# watch_rev3.net
KiCad netlist of a schematic drawn in EAGLE
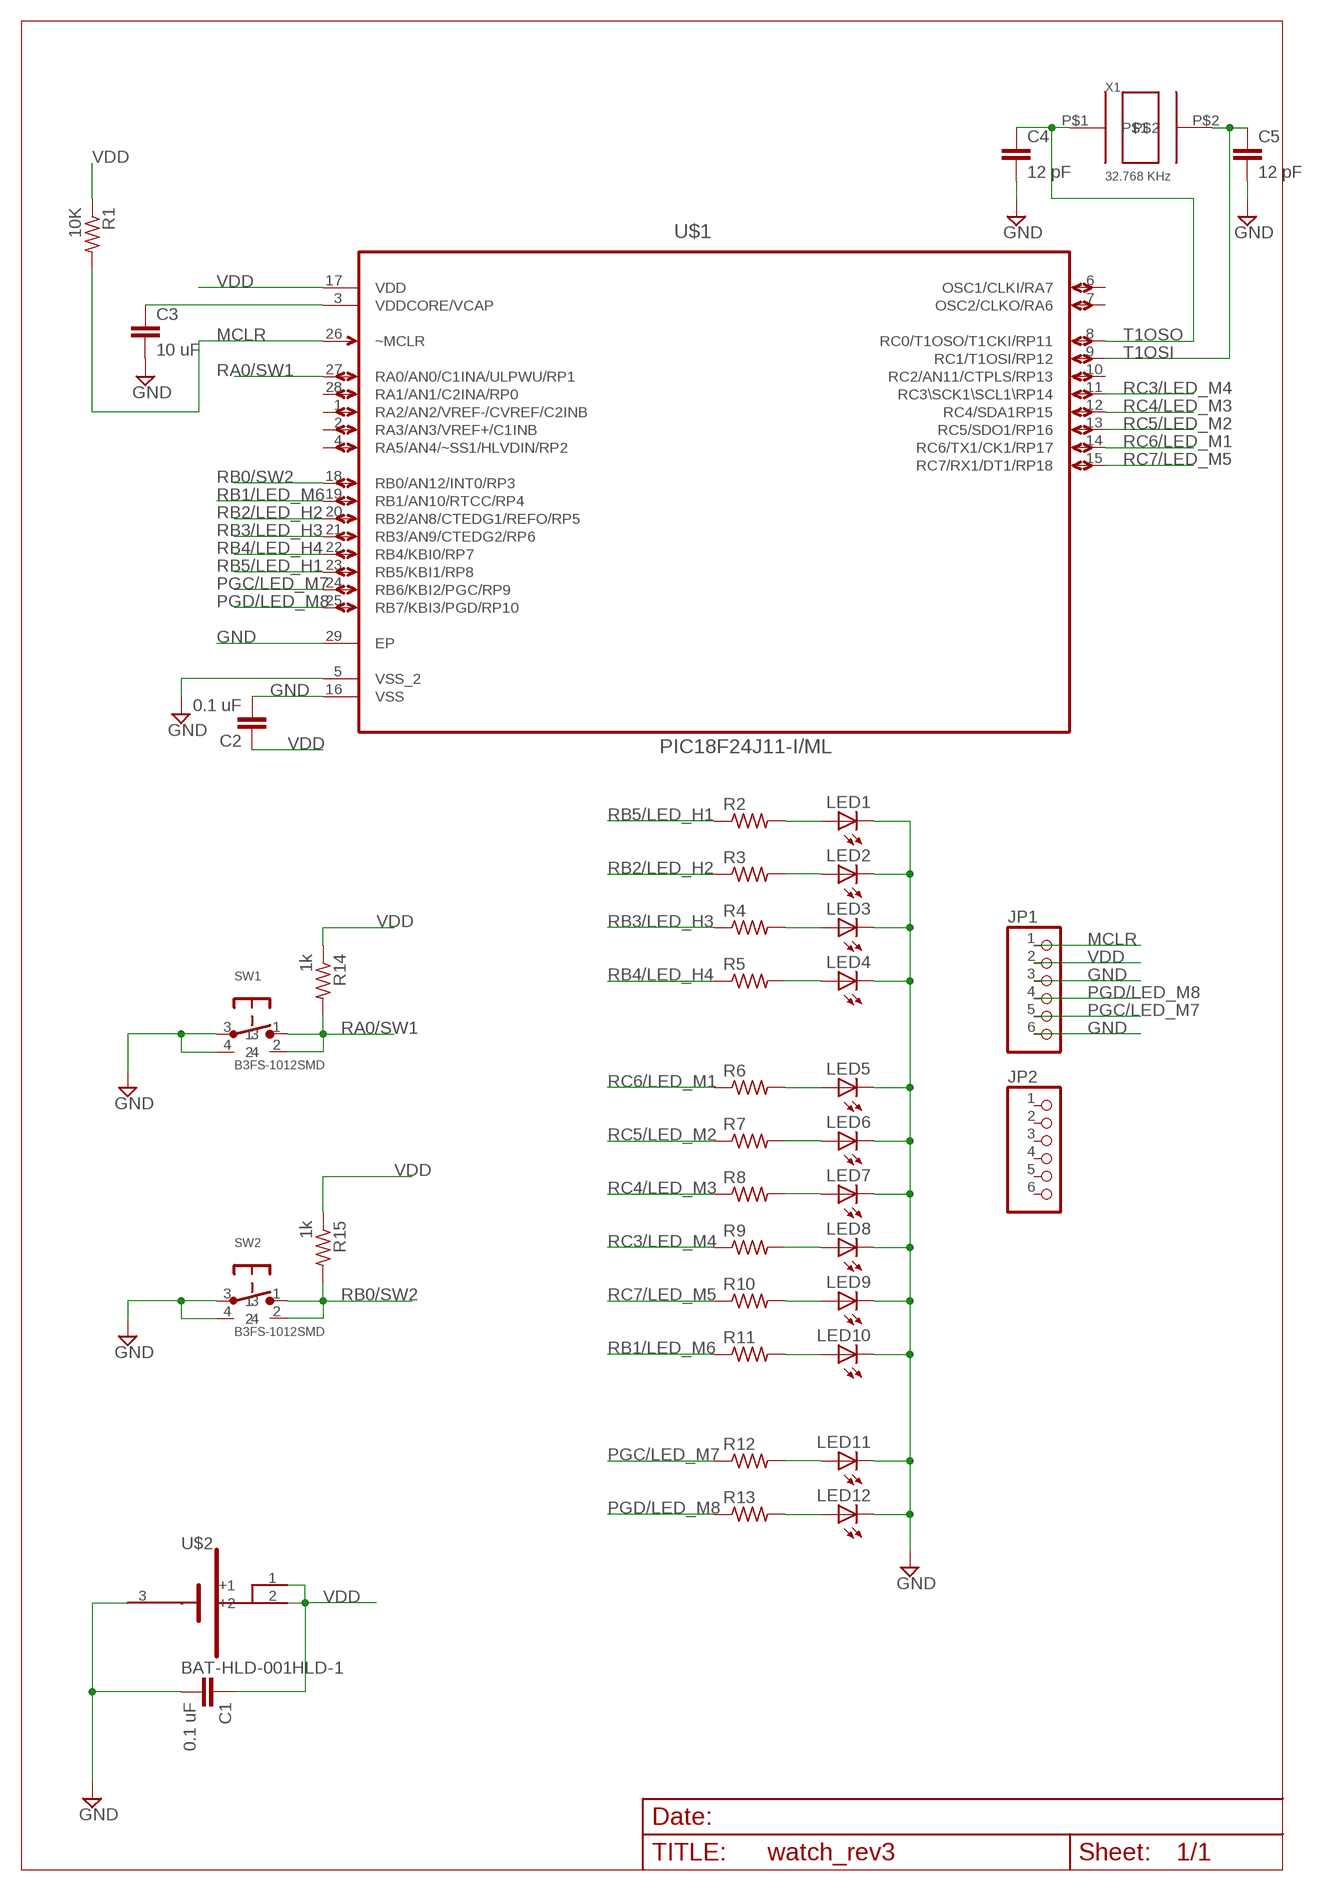
[diagram p0: schematic, sheet 1]

(export (version "E")
  (design (tool "Eeschema 10.0.6"))
  (components
    (comp (ref "C1")
      (value "0.1 uF")
      (footprint "eagle-import:C0603")
      (libsource (lib "eagle-import") (part "C-EUC0603"))
    )
    (comp (ref "C2")
      (value "0.1 uF")
      (footprint "eagle-import:C0603")
      (libsource (lib "eagle-import") (part "C-EUC0603"))
    )
    (comp (ref "C3")
      (value "10 uF")
      (footprint "eagle-import:C0603")
      (libsource (lib "eagle-import") (part "C-EUC0603"))
    )
    (comp (ref "C4")
      (value "12 pF")
      (footprint "eagle-import:C0603")
      (libsource (lib "eagle-import") (part "C-EUC0603"))
    )
    (comp (ref "C5")
      (value "12 pF")
      (footprint "eagle-import:C0603")
      (libsource (lib "eagle-import") (part "C-EUC0603"))
    )
    (comp (ref "JP1")
      (value "PINHD-1X6")
      (footprint "eagle-import:1X06")
      (libsource (lib "eagle-import") (part "PINHD-1X6"))
    )
    (comp (ref "JP2")
      (value "PINHD-1X6")
      (footprint "eagle-import:1X06")
      (libsource (lib "eagle-import") (part "PINHD-1X6"))
    )
    (comp (ref "LED1")
      (value "LEDCHIPLED_0603")
      (footprint "eagle-import:CHIPLED_0603")
      (libsource (lib "eagle-import") (part "LEDCHIPLED_0603"))
    )
    (comp (ref "LED2")
      (value "LEDCHIPLED_0603")
      (footprint "eagle-import:CHIPLED_0603")
      (libsource (lib "eagle-import") (part "LEDCHIPLED_0603"))
    )
    (comp (ref "LED3")
      (value "LEDCHIPLED_0603")
      (footprint "eagle-import:CHIPLED_0603")
      (libsource (lib "eagle-import") (part "LEDCHIPLED_0603"))
    )
    (comp (ref "LED4")
      (value "LEDCHIPLED_0603")
      (footprint "eagle-import:CHIPLED_0603")
      (libsource (lib "eagle-import") (part "LEDCHIPLED_0603"))
    )
    (comp (ref "LED5")
      (value "LEDCHIPLED_0603")
      (footprint "eagle-import:CHIPLED_0603")
      (libsource (lib "eagle-import") (part "LEDCHIPLED_0603"))
    )
    (comp (ref "LED6")
      (value "LEDCHIPLED_0603")
      (footprint "eagle-import:CHIPLED_0603")
      (libsource (lib "eagle-import") (part "LEDCHIPLED_0603"))
    )
    (comp (ref "LED7")
      (value "LEDCHIPLED_0603")
      (footprint "eagle-import:CHIPLED_0603")
      (libsource (lib "eagle-import") (part "LEDCHIPLED_0603"))
    )
    (comp (ref "LED8")
      (value "LEDCHIPLED_0603")
      (footprint "eagle-import:CHIPLED_0603")
      (libsource (lib "eagle-import") (part "LEDCHIPLED_0603"))
    )
    (comp (ref "LED9")
      (value "LEDCHIPLED_0603")
      (footprint "eagle-import:CHIPLED_0603")
      (libsource (lib "eagle-import") (part "LEDCHIPLED_0603"))
    )
    (comp (ref "LED10")
      (value "LEDCHIPLED_0603")
      (footprint "eagle-import:CHIPLED_0603")
      (libsource (lib "eagle-import") (part "LEDCHIPLED_0603"))
    )
    (comp (ref "LED11")
      (value "LEDCHIPLED_0603")
      (footprint "eagle-import:CHIPLED_0603")
      (libsource (lib "eagle-import") (part "LEDCHIPLED_0603"))
    )
    (comp (ref "LED12")
      (value "LEDCHIPLED_0603")
      (footprint "eagle-import:CHIPLED_0603")
      (libsource (lib "eagle-import") (part "LEDCHIPLED_0603"))
    )
    (comp (ref "R1")
      (value "10K")
      (footprint "eagle-import:R0603")
      (libsource (lib "eagle-import") (part "R-US_R0603"))
    )
    (comp (ref "R2")
      (value "R-US_R0603")
      (footprint "eagle-import:R0603")
      (libsource (lib "eagle-import") (part "R-US_R0603"))
    )
    (comp (ref "R3")
      (value "R-US_R0603")
      (footprint "eagle-import:R0603")
      (libsource (lib "eagle-import") (part "R-US_R0603"))
    )
    (comp (ref "R4")
      (value "R-US_R0603")
      (footprint "eagle-import:R0603")
      (libsource (lib "eagle-import") (part "R-US_R0603"))
    )
    (comp (ref "R5")
      (value "R-US_R0603")
      (footprint "eagle-import:R0603")
      (libsource (lib "eagle-import") (part "R-US_R0603"))
    )
    (comp (ref "R6")
      (value "R-US_R0603")
      (footprint "eagle-import:R0603")
      (libsource (lib "eagle-import") (part "R-US_R0603"))
    )
    (comp (ref "R7")
      (value "R-US_R0603")
      (footprint "eagle-import:R0603")
      (libsource (lib "eagle-import") (part "R-US_R0603"))
    )
    (comp (ref "R8")
      (value "R-US_R0603")
      (footprint "eagle-import:R0603")
      (libsource (lib "eagle-import") (part "R-US_R0603"))
    )
    (comp (ref "R9")
      (value "R-US_R0603")
      (footprint "eagle-import:R0603")
      (libsource (lib "eagle-import") (part "R-US_R0603"))
    )
    (comp (ref "R10")
      (value "R-US_R0603")
      (footprint "eagle-import:R0603")
      (libsource (lib "eagle-import") (part "R-US_R0603"))
    )
    (comp (ref "R11")
      (value "R-US_R0603")
      (footprint "eagle-import:R0603")
      (libsource (lib "eagle-import") (part "R-US_R0603"))
    )
    (comp (ref "R12")
      (value "R-US_R0603")
      (footprint "eagle-import:R0603")
      (libsource (lib "eagle-import") (part "R-US_R0603"))
    )
    (comp (ref "R13")
      (value "R-US_R0603")
      (footprint "eagle-import:R0603")
      (libsource (lib "eagle-import") (part "R-US_R0603"))
    )
    (comp (ref "R14")
      (value "1k")
      (footprint "eagle-import:R0603")
      (libsource (lib "eagle-import") (part "R-US_R0603"))
    )
    (comp (ref "R15")
      (value "1k")
      (footprint "eagle-import:R0603")
      (libsource (lib "eagle-import") (part "R-US_R0603"))
    )
    (comp (ref "SW1")
      (value "B3FS-1012SMD")
      (footprint "eagle-import:B3FS-1012")
      (libsource (lib "eagle-import") (part "B3FS-1012SMD"))
    )
    (comp (ref "SW2")
      (value "B3FS-1012SMD")
      (footprint "eagle-import:B3FS-1012")
      (libsource (lib "eagle-import") (part "B3FS-1012SMD"))
    )
    (comp (ref "U$1")
      (value "PIC18F24J11-I/ML")
      (footprint "eagle-import:QFN65P600X600X100-29N")
      (fields (field (name "MPN") "PIC18F24J11-I/Ml"))
      (libsource (lib "eagle-import") (part "PIC18F24J11-I/ML"))
    )
    (comp (ref "U$2")
      (value "BAT-HLD-001HLD-1")
      (footprint "eagle-import:BAT-HLD-001")
      (libsource (lib "eagle-import") (part "BAT-HLD-001HLD-1"))
    )
    (comp (ref "X1")
      (value "32.768 KHz")
      (footprint "eagle-import:XTAL_3.2X1.5")
      (libsource (lib "eagle-import") (part "ST3215SB32768E0HPWBB"))
    )
  )
  (nets
    (net (code "1") (name "/MCLR") (class "Default")
      (node (ref "JP1") (pin "1") (pinfunction "1_1") (pintype "passive"))
      (node (ref "R1") (pin "2") (pinfunction "2_2") (pintype "passive"))
      (node (ref "U$1") (pin "26") (pinfunction "~{MCLR}_26") (pintype "input"))
    )
    (net (code "2") (name "/PGC{slash}LED_M7") (class "Default")
      (node (ref "JP1") (pin "5") (pinfunction "5_5") (pintype "passive"))
      (node (ref "R12") (pin "1") (pinfunction "1_1") (pintype "passive"))
      (node (ref "U$1") (pin "24") (pinfunction "RB6/KBI2/PGC/RP9_24") (pintype "bidirectional"))
    )
    (net (code "3") (name "/PGD{slash}LED_M8") (class "Default")
      (node (ref "JP1") (pin "4") (pinfunction "4_4") (pintype "passive"))
      (node (ref "R13") (pin "1") (pinfunction "1_1") (pintype "passive"))
      (node (ref "U$1") (pin "25") (pinfunction "RB7/KBI3/PGD/RP10_25") (pintype "bidirectional"))
    )
    (net (code "4") (name "/RA0{slash}SW1") (class "Default")
      (node (ref "R14") (pin "2") (pinfunction "2_2") (pintype "passive"))
      (node (ref "SW1") (pin "1") (pinfunction "1_1") (pintype "bidirectional"))
      (node (ref "SW1") (pin "2") (pinfunction "2_2") (pintype "bidirectional"))
      (node (ref "U$1") (pin "27") (pinfunction "RA0/AN0/C1INA/ULPWU/RP1_27") (pintype "bidirectional"))
    )
    (net (code "5") (name "/RB0{slash}SW2") (class "Default")
      (node (ref "R15") (pin "2") (pinfunction "2_2") (pintype "passive"))
      (node (ref "SW2") (pin "1") (pinfunction "1_1") (pintype "bidirectional"))
      (node (ref "SW2") (pin "2") (pinfunction "2_2") (pintype "bidirectional"))
      (node (ref "U$1") (pin "18") (pinfunction "RB0/AN12/INT0/RP3_18") (pintype "bidirectional"))
    )
    (net (code "6") (name "/RB1{slash}LED_M6") (class "Default")
      (node (ref "R11") (pin "1") (pinfunction "1_1") (pintype "passive"))
      (node (ref "U$1") (pin "19") (pinfunction "RB1/AN10/RTCC/RP4_19") (pintype "bidirectional"))
    )
    (net (code "7") (name "/RB2{slash}LED_H2") (class "Default")
      (node (ref "R3") (pin "1") (pinfunction "1_1") (pintype "passive"))
      (node (ref "U$1") (pin "20") (pinfunction "RB2/AN8/CTEDG1/REFO/RP5_20") (pintype "bidirectional"))
    )
    (net (code "8") (name "/RB3{slash}LED_H3") (class "Default")
      (node (ref "R4") (pin "1") (pinfunction "1_1") (pintype "passive"))
      (node (ref "U$1") (pin "21") (pinfunction "RB3/AN9/CTEDG2/RP6_21") (pintype "bidirectional"))
    )
    (net (code "9") (name "/RB4{slash}LED_H4") (class "Default")
      (node (ref "R5") (pin "1") (pinfunction "1_1") (pintype "passive"))
      (node (ref "U$1") (pin "22") (pinfunction "RB4/KBI0/RP7_22") (pintype "bidirectional"))
    )
    (net (code "10") (name "/RB5{slash}LED_H1") (class "Default")
      (node (ref "R2") (pin "1") (pinfunction "1_1") (pintype "passive"))
      (node (ref "U$1") (pin "23") (pinfunction "RB5/KBI1/RP8_23") (pintype "bidirectional"))
    )
    (net (code "11") (name "/RC3{slash}LED_M4") (class "Default")
      (node (ref "R9") (pin "1") (pinfunction "1_1") (pintype "passive"))
      (node (ref "U$1") (pin "11") (pinfunction "RC3\\SCK1\\SCL1\\RP14_11") (pintype "bidirectional"))
    )
    (net (code "12") (name "/RC4{slash}LED_M3") (class "Default")
      (node (ref "R8") (pin "1") (pinfunction "1_1") (pintype "passive"))
      (node (ref "U$1") (pin "12") (pinfunction "RC4/SDA1RP15_12") (pintype "bidirectional"))
    )
    (net (code "13") (name "/RC5{slash}LED_M2") (class "Default")
      (node (ref "R7") (pin "1") (pinfunction "1_1") (pintype "passive"))
      (node (ref "U$1") (pin "13") (pinfunction "RC5/SDO1/RP16_13") (pintype "bidirectional"))
    )
    (net (code "14") (name "/RC6{slash}LED_M1") (class "Default")
      (node (ref "R6") (pin "1") (pinfunction "1_1") (pintype "passive"))
      (node (ref "U$1") (pin "14") (pinfunction "RC6/TX1/CK1/RP17_14") (pintype "bidirectional"))
    )
    (net (code "15") (name "/RC7{slash}LED_M5") (class "Default")
      (node (ref "R10") (pin "1") (pinfunction "1_1") (pintype "passive"))
      (node (ref "U$1") (pin "15") (pinfunction "RC7/RX1/DT1/RP18_15") (pintype "bidirectional"))
    )
    (net (code "16") (name "/T1OSI") (class "Default")
      (node (ref "C5") (pin "1") (pinfunction "1_1") (pintype "passive"))
      (node (ref "U$1") (pin "9") (pinfunction "RC1/T1OSI/RP12_9") (pintype "bidirectional"))
      (node (ref "X1") (pin "P$2") (pinfunction "P$2_P$2") (pintype "bidirectional"))
    )
    (net (code "17") (name "/T1OSO") (class "Default")
      (node (ref "C4") (pin "1") (pinfunction "1_1") (pintype "passive"))
      (node (ref "U$1") (pin "8") (pinfunction "RC0/T1OSO/T1CKI/RP11_8") (pintype "bidirectional"))
      (node (ref "X1") (pin "P$1") (pinfunction "P$1_P$1") (pintype "bidirectional"))
    )
    (net (code "18") (name "/VDD") (class "Default")
      (node (ref "C1") (pin "1") (pinfunction "1_1") (pintype "passive"))
      (node (ref "C2") (pin "1") (pinfunction "1_1") (pintype "passive"))
      (node (ref "JP1") (pin "2") (pinfunction "2_2") (pintype "passive"))
      (node (ref "R1") (pin "1") (pinfunction "1_1") (pintype "passive"))
      (node (ref "R14") (pin "1") (pinfunction "1_1") (pintype "passive"))
      (node (ref "R15") (pin "1") (pinfunction "1_1") (pintype "passive"))
      (node (ref "U$1") (pin "17") (pinfunction "VDD_17") (pintype "power_in"))
      (node (ref "U$2") (pin "1") (pinfunction "+1_1") (pintype "bidirectional"))
      (node (ref "U$2") (pin "2") (pinfunction "+2_2") (pintype "bidirectional"))
    )
    (net (code "19") (name "GND") (class "Default")
      (node (ref "C1") (pin "2") (pinfunction "2_2") (pintype "passive"))
      (node (ref "C2") (pin "2") (pinfunction "2_2") (pintype "passive"))
      (node (ref "C3") (pin "2") (pinfunction "2_2") (pintype "passive"))
      (node (ref "C4") (pin "2") (pinfunction "2_2") (pintype "passive"))
      (node (ref "C5") (pin "2") (pinfunction "2_2") (pintype "passive"))
      (node (ref "JP1") (pin "3") (pinfunction "3_3") (pintype "passive"))
      (node (ref "JP1") (pin "6") (pinfunction "6_6") (pintype "passive"))
      (node (ref "LED1") (pin "C") (pinfunction "C_C") (pintype "passive"))
      (node (ref "LED10") (pin "C") (pinfunction "C_C") (pintype "passive"))
      (node (ref "LED11") (pin "C") (pinfunction "C_C") (pintype "passive"))
      (node (ref "LED12") (pin "C") (pinfunction "C_C") (pintype "passive"))
      (node (ref "LED2") (pin "C") (pinfunction "C_C") (pintype "passive"))
      (node (ref "LED3") (pin "C") (pinfunction "C_C") (pintype "passive"))
      (node (ref "LED4") (pin "C") (pinfunction "C_C") (pintype "passive"))
      (node (ref "LED5") (pin "C") (pinfunction "C_C") (pintype "passive"))
      (node (ref "LED6") (pin "C") (pinfunction "C_C") (pintype "passive"))
      (node (ref "LED7") (pin "C") (pinfunction "C_C") (pintype "passive"))
      (node (ref "LED8") (pin "C") (pinfunction "C_C") (pintype "passive"))
      (node (ref "LED9") (pin "C") (pinfunction "C_C") (pintype "passive"))
      (node (ref "SW1") (pin "3") (pinfunction "3_3") (pintype "bidirectional"))
      (node (ref "SW1") (pin "4") (pinfunction "4_4") (pintype "bidirectional"))
      (node (ref "SW2") (pin "3") (pinfunction "3_3") (pintype "bidirectional"))
      (node (ref "SW2") (pin "4") (pinfunction "4_4") (pintype "bidirectional"))
      (node (ref "U$1") (pin "16") (pinfunction "VSS_16") (pintype "passive"))
      (node (ref "U$1") (pin "29") (pinfunction "EP_29") (pintype "passive"))
      (node (ref "U$1") (pin "5") (pinfunction "VSS_2_5") (pintype "passive"))
      (node (ref "U$2") (pin "3") (pinfunction "-_3") (pintype "bidirectional"))
    )
    (net (code "20") (name "Net-(LED1-PadA)") (class "Default")
      (node (ref "LED1") (pin "A") (pinfunction "A_A") (pintype "passive"))
      (node (ref "R2") (pin "2") (pinfunction "2_2") (pintype "passive"))
    )
    (net (code "21") (name "Net-(LED2-PadA)") (class "Default")
      (node (ref "LED2") (pin "A") (pinfunction "A_A") (pintype "passive"))
      (node (ref "R3") (pin "2") (pinfunction "2_2") (pintype "passive"))
    )
    (net (code "22") (name "Net-(LED3-PadA)") (class "Default")
      (node (ref "LED3") (pin "A") (pinfunction "A_A") (pintype "passive"))
      (node (ref "R4") (pin "2") (pinfunction "2_2") (pintype "passive"))
    )
    (net (code "23") (name "Net-(LED4-PadA)") (class "Default")
      (node (ref "LED4") (pin "A") (pinfunction "A_A") (pintype "passive"))
      (node (ref "R5") (pin "2") (pinfunction "2_2") (pintype "passive"))
    )
    (net (code "24") (name "Net-(LED5-PadA)") (class "Default")
      (node (ref "LED5") (pin "A") (pinfunction "A_A") (pintype "passive"))
      (node (ref "R6") (pin "2") (pinfunction "2_2") (pintype "passive"))
    )
    (net (code "25") (name "Net-(LED6-PadA)") (class "Default")
      (node (ref "LED6") (pin "A") (pinfunction "A_A") (pintype "passive"))
      (node (ref "R7") (pin "2") (pinfunction "2_2") (pintype "passive"))
    )
    (net (code "26") (name "Net-(LED7-PadA)") (class "Default")
      (node (ref "LED7") (pin "A") (pinfunction "A_A") (pintype "passive"))
      (node (ref "R8") (pin "2") (pinfunction "2_2") (pintype "passive"))
    )
    (net (code "27") (name "Net-(LED8-PadA)") (class "Default")
      (node (ref "LED8") (pin "A") (pinfunction "A_A") (pintype "passive"))
      (node (ref "R9") (pin "2") (pinfunction "2_2") (pintype "passive"))
    )
    (net (code "28") (name "Net-(LED9-PadA)") (class "Default")
      (node (ref "LED9") (pin "A") (pinfunction "A_A") (pintype "passive"))
      (node (ref "R10") (pin "2") (pinfunction "2_2") (pintype "passive"))
    )
    (net (code "29") (name "Net-(LED10-PadA)") (class "Default")
      (node (ref "LED10") (pin "A") (pinfunction "A_A") (pintype "passive"))
      (node (ref "R11") (pin "2") (pinfunction "2_2") (pintype "passive"))
    )
    (net (code "30") (name "Net-(LED11-PadA)") (class "Default")
      (node (ref "LED11") (pin "A") (pinfunction "A_A") (pintype "passive"))
      (node (ref "R12") (pin "2") (pinfunction "2_2") (pintype "passive"))
    )
    (net (code "31") (name "Net-(LED12-PadA)") (class "Default")
      (node (ref "LED12") (pin "A") (pinfunction "A_A") (pintype "passive"))
      (node (ref "R13") (pin "2") (pinfunction "2_2") (pintype "passive"))
    )
    (net (code "32") (name "Net-(U$1-VDDCORE{slash}VCAP)") (class "Default")
      (node (ref "C3") (pin "1") (pinfunction "1_1") (pintype "passive"))
      (node (ref "U$1") (pin "3") (pinfunction "VDDCORE/VCAP_3") (pintype "power_in"))
    )
    (net (code "33") (name "unconnected-(JP2-Pad1)") (class "Default")
      (node (ref "JP2") (pin "1") (pinfunction "1_1") (pintype "passive"))
    )
    (net (code "34") (name "unconnected-(JP2-Pad2)") (class "Default")
      (node (ref "JP2") (pin "2") (pinfunction "2_2") (pintype "passive"))
    )
    (net (code "35") (name "unconnected-(JP2-Pad3)") (class "Default")
      (node (ref "JP2") (pin "3") (pinfunction "3_3") (pintype "passive"))
    )
    (net (code "36") (name "unconnected-(JP2-Pad4)") (class "Default")
      (node (ref "JP2") (pin "4") (pinfunction "4_4") (pintype "passive"))
    )
    (net (code "37") (name "unconnected-(JP2-Pad5)") (class "Default")
      (node (ref "JP2") (pin "5") (pinfunction "5_5") (pintype "passive"))
    )
    (net (code "38") (name "unconnected-(JP2-Pad6)") (class "Default")
      (node (ref "JP2") (pin "6") (pinfunction "6_6") (pintype "passive"))
    )
    (net (code "39") (name "unconnected-(U$1-OSC1{slash}CLKI{slash}RA7-Pad6)") (class "Default")
      (node (ref "U$1") (pin "6") (pinfunction "OSC1/CLKI/RA7_6") (pintype "bidirectional"))
    )
    (net (code "40") (name "unconnected-(U$1-OSC2{slash}CLKO{slash}RA6-Pad7)") (class "Default")
      (node (ref "U$1") (pin "7") (pinfunction "OSC2/CLKO/RA6_7") (pintype "bidirectional"))
    )
    (net (code "41") (name "unconnected-(U$1-RA1{slash}AN1{slash}C2INA{slash}RP0-Pad28)") (class "Default")
      (node (ref "U$1") (pin "28") (pinfunction "RA1/AN1/C2INA/RP0_28") (pintype "bidirectional"))
    )
    (net (code "42") (name "unconnected-(U$1-RA2{slash}AN2{slash}VREF-{slash}CVREF{slash}C2INB-Pad1)") (class "Default")
      (node (ref "U$1") (pin "1") (pinfunction "RA2/AN2/VREF-/CVREF/C2INB_1") (pintype "bidirectional"))
    )
    (net (code "43") (name "unconnected-(U$1-RA3{slash}AN3{slash}VREF+{slash}C1INB-Pad2)") (class "Default")
      (node (ref "U$1") (pin "2") (pinfunction "RA3/AN3/VREF+/C1INB_2") (pintype "bidirectional"))
    )
    (net (code "44") (name "unconnected-(U$1-RA5{slash}AN4{slash}~{SS1{slash}HLVDIN{slash}RP2}-Pad4)") (class "Default")
      (node (ref "U$1") (pin "4") (pinfunction "RA5/AN4/~{SS1/HLVDIN/RP2}_4") (pintype "bidirectional"))
    )
    (net (code "45") (name "unconnected-(U$1-RC2{slash}AN11{slash}CTPLS{slash}RP13-Pad10)") (class "Default")
      (node (ref "U$1") (pin "10") (pinfunction "RC2/AN11/CTPLS/RP13_10") (pintype "bidirectional"))
    )
  )
)
